# Rev05MergeRedux--External_IO_Protection.net
KiCad netlist of a schematic drawn in Altium Designer
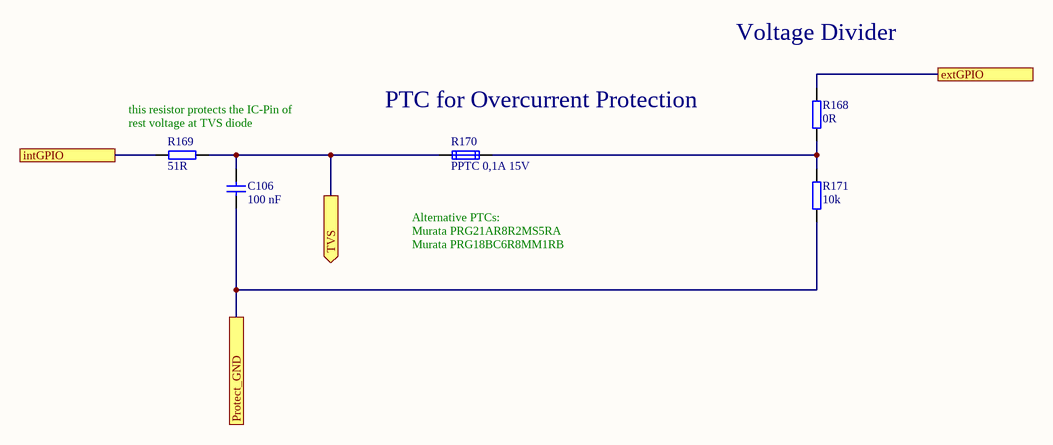
[diagram p0: Rev05MergeRedux--External_IO_Protection.SchDoc]

(export (version "E")
  (design (tool "Eeschema 10.0.6"))
  (components
    (comp (ref "C106")
      (value "100 nF")
      (footprint "C_0603_TE")
      (description "Generic capacitor")
      (fields
        (field (name "TOLERANCE") "10 %")
        (field (name "VOLTAGE") "50 V")
        (field (name "CREATED FROM") "AGeiger")
      )
      (libsource (lib "user") (part "CAP-NP"))
    )
    (comp (ref "R168")
      (value "0R")
      (footprint "R_0603_TE")
      (description "Generic resistor")
      (fields
        (field (name "TOLERANCE") "1 %")
        (field (name "MANUFACTURER PART NUMBER") "UZgen_R_0603_0R")
        (field (name "CREATED FROM") "UZgenTool")
      )
      (libsource (lib "user") (part "RES"))
    )
    (comp (ref "R169")
      (value "51R")
      (footprint "RESC1608X55N_V")
      (description "WID SMD 51R 1% 0,1W  BF 1608 (0603)")
      (fields (field (name "TOLERANCE") "1%"))
      (libsource (lib "TE") (part "RES"))
    )
    (comp (ref "R170")
      (value "PPTC 0,1A 15V")
      (footprint "RESC2012X85N")
      (description "PTC Resettable Fuse 0.1A 15V SMD 0805")
      (fields (field (name "VOLTAGE") "15V"))
      (libsource (lib "TE") (part "Polyswitch"))
    )
    (comp (ref "R171")
      (value "10k")
      (footprint "R_0603_TE")
      (description "Generic resistor")
      (fields
        (field (name "TOLERANCE") "1 %")
        (field (name "MANUFACTURER PART NUMBER") "UZgen_R_0603_10k")
        (field (name "CREATED FROM") "AGeiger")
      )
      (libsource (lib "user") (part "RES"))
    )
  )
  (nets
    (net (code "1") (name "/Protect_GND") (class "Default")
      (node (ref "C106") (pin "1") (pinfunction "1_1") (pintype "passive"))
      (node (ref "R171") (pin "2") (pinfunction "2_2") (pintype "passive"))
    )
    (net (code "2") (name "/TVS") (class "Default")
      (node (ref "C106") (pin "2") (pinfunction "2_2") (pintype "passive"))
      (node (ref "R169") (pin "1") (pinfunction "1_1") (pintype "passive"))
      (node (ref "R170") (pin "1") (pinfunction "1_1") (pintype "passive"))
    )
    (net (code "3") (name "/extGPIO") (class "Default")
      (node (ref "R168") (pin "2") (pinfunction "2_2") (pintype "passive"))
    )
    (net (code "4") (name "/intGPIO") (class "Default")
      (node (ref "R169") (pin "2") (pinfunction "2_2") (pintype "passive"))
    )
    (net (code "5") (name "Net-(R168-Pad1)") (class "Default")
      (node (ref "R168") (pin "1") (pinfunction "1_1") (pintype "passive"))
      (node (ref "R170") (pin "2") (pinfunction "2_2") (pintype "passive"))
      (node (ref "R171") (pin "1") (pinfunction "1_1") (pintype "passive"))
    )
  )
)
